# Minimal-Driver.net
KiCad netlist of a schematic drawn in EAGLE
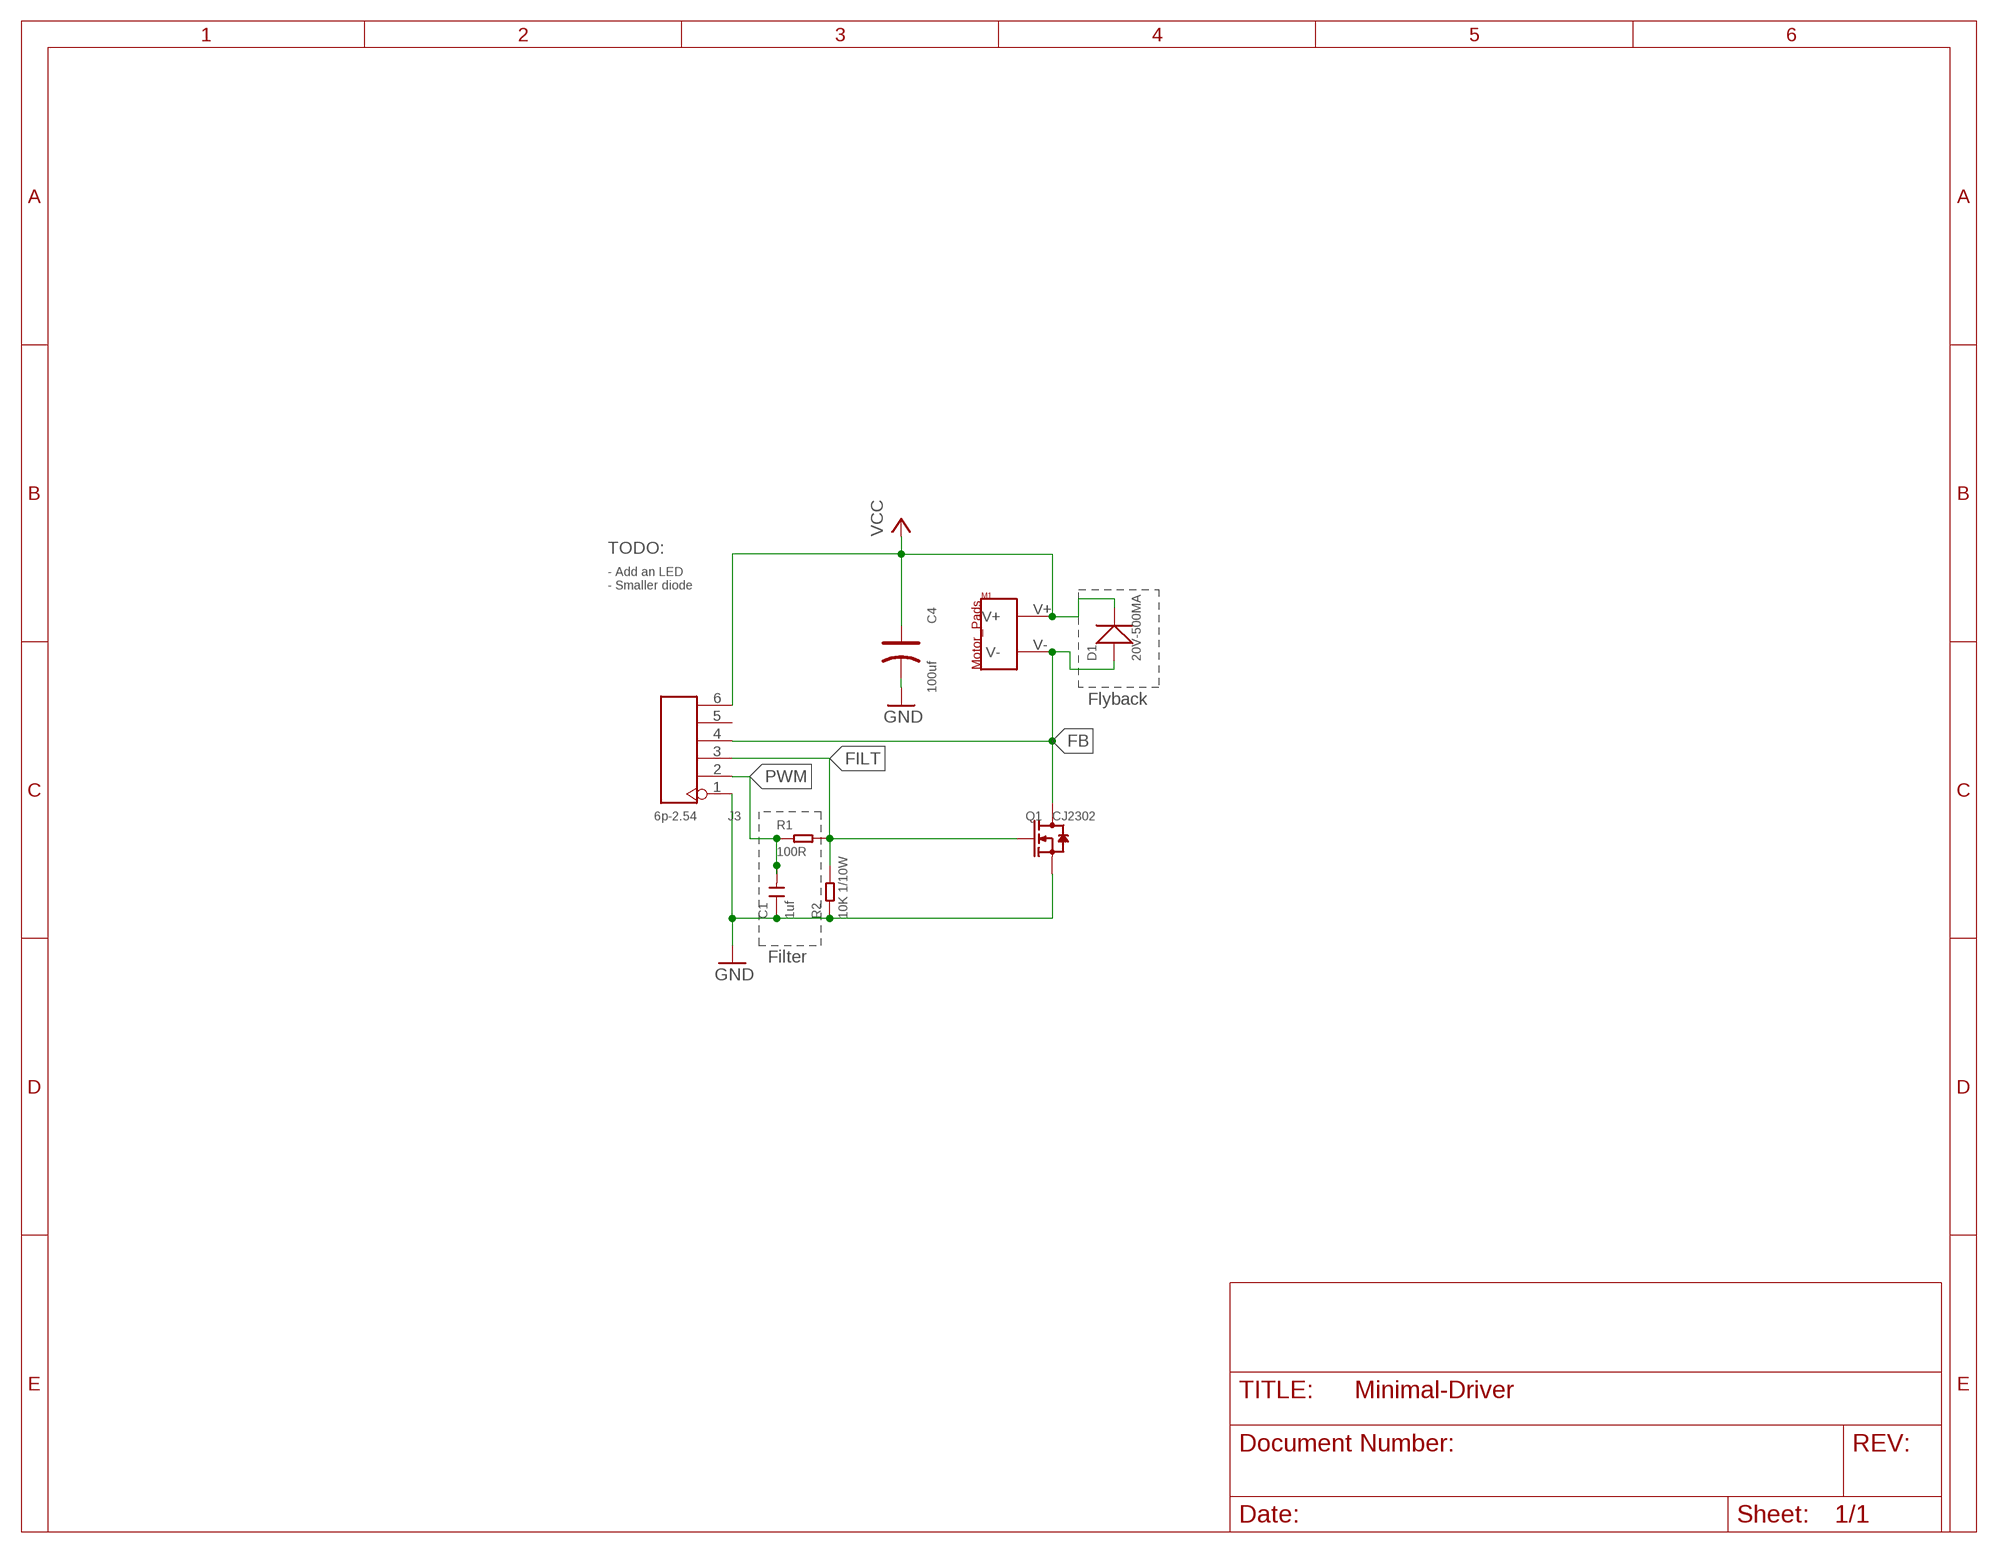
[diagram p0: schematic, sheet 1]

(export (version "E")
  (design (tool "Eeschema 10.0.6"))
  (components
    (comp (ref "C1")
      (value "1uf")
      (footprint "eagle-import:C0402")
      (fields (field (name "MPN") "CC0402KRX5R6BB105"))
      (libsource (lib "eagle-import") (part "CERAMIC-1UF-10V-10%-X5R(0402)"))
    )
    (comp (ref "C4")
      (value "100uf")
      (footprint "eagle-import:AVX-B")
      (fields (field (name "MPN") "TAJB107M010#NJ"))
      (libsource (lib "eagle-import") (part "TANTALUM-SMD-100UF-10V(AVX-B)"))
    )
    (comp (ref "D1")
      (value "20V-500MA")
      (footprint "eagle-import:SOD-123")
      (fields (field (name "MPN") "SS0520-7-F"))
      (libsource (lib "eagle-import") (part "SMD-DIODE-SCHOTTKY-20V-500MA(SOD-123)"))
    )
    (comp (ref "J3")
      (value "6p-2.54")
      (footprint "eagle-import:H6-2.54")
      (fields (field (name "MPN") "P125-1106A1BS116A1"))
      (libsource (lib "eagle-import") (part "DIP-BLACK-MALE-HEADER(6P-2.54)"))
    )
    (comp (ref "M1")
      (value "MOTOR_PADS")
      (footprint "eagle-import:MOTOR_PADS")
      (libsource (lib "eagle-import") (part "MOTOR_PADS"))
    )
    (comp (ref "Q1")
      (value "CJ2302")
      (footprint "eagle-import:SOT-23")
      (libsource (lib "eagle-import") (part "SMD-MOSFET-N-CH-20V-2.1A-CJ2302(SOT-23)"))
    )
    (comp (ref "R1")
      (value "100R")
      (footprint "eagle-import:R0603")
      (fields (field (name "MPN") "RC0603JR-07100RL"))
      (libsource (lib "eagle-import") (part "SMD-RES-100R-5%-1/10W(0603)"))
    )
    (comp (ref "R2")
      (value "10K 1/10W")
      (footprint "eagle-import:R0603")
      (fields (field (name "MPN") "RC0603JR-0710KL"))
      (libsource (lib "eagle-import") (part "SMD-RES-10K-5%-1/10W(0603)"))
    )
  )
  (nets
    (net (code "1") (name "FB") (class "Default")
      (node (ref "D1") (pin "+") (pinfunction "+_+") (pintype "passive"))
      (node (ref "J3") (pin "4") (pinfunction "4_4") (pintype "bidirectional"))
      (node (ref "M1") (pin "V-") (pinfunction "V-_V-") (pintype "bidirectional"))
      (node (ref "Q1") (pin "3") (pinfunction "D_3") (pintype "passive"))
    )
    (net (code "2") (name "FILT") (class "Default")
      (node (ref "J3") (pin "3") (pinfunction "3_3") (pintype "bidirectional"))
      (node (ref "Q1") (pin "1") (pinfunction "G_1") (pintype "passive"))
      (node (ref "R1") (pin "2") (pinfunction "2_2") (pintype "passive"))
      (node (ref "R2") (pin "2") (pinfunction "2_2") (pintype "passive"))
    )
    (net (code "3") (name "GND") (class "Default")
      (node (ref "C1") (pin "1") (pinfunction "1_1") (pintype "passive"))
      (node (ref "C4") (pin "-") (pinfunction "-_-") (pintype "passive"))
      (node (ref "J3") (pin "1") (pinfunction "1_1") (pintype "bidirectional"))
      (node (ref "Q1") (pin "2") (pinfunction "S_2") (pintype "passive"))
      (node (ref "R2") (pin "1") (pinfunction "1_1") (pintype "passive"))
    )
    (net (code "4") (name "PWM") (class "Default")
      (node (ref "C1") (pin "2") (pinfunction "2_2") (pintype "passive"))
      (node (ref "J3") (pin "2") (pinfunction "2_2") (pintype "bidirectional"))
      (node (ref "R1") (pin "1") (pinfunction "1_1") (pintype "passive"))
    )
    (net (code "5") (name "VCC") (class "Default")
      (node (ref "C4") (pin "+") (pinfunction "+_+") (pintype "passive"))
      (node (ref "D1") (pin "-") (pinfunction "-_-") (pintype "passive"))
      (node (ref "J3") (pin "6") (pinfunction "6_6") (pintype "bidirectional"))
      (node (ref "M1") (pin "V+") (pinfunction "V+_V+") (pintype "bidirectional"))
    )
    (net (code "6") (name "unconnected-(J3-Pad5)") (class "Default")
      (node (ref "J3") (pin "5") (pinfunction "5_5") (pintype "bidirectional"))
    )
  )
)
